# 1.net
KiCad netlist of a schematic drawn in Altium Designer
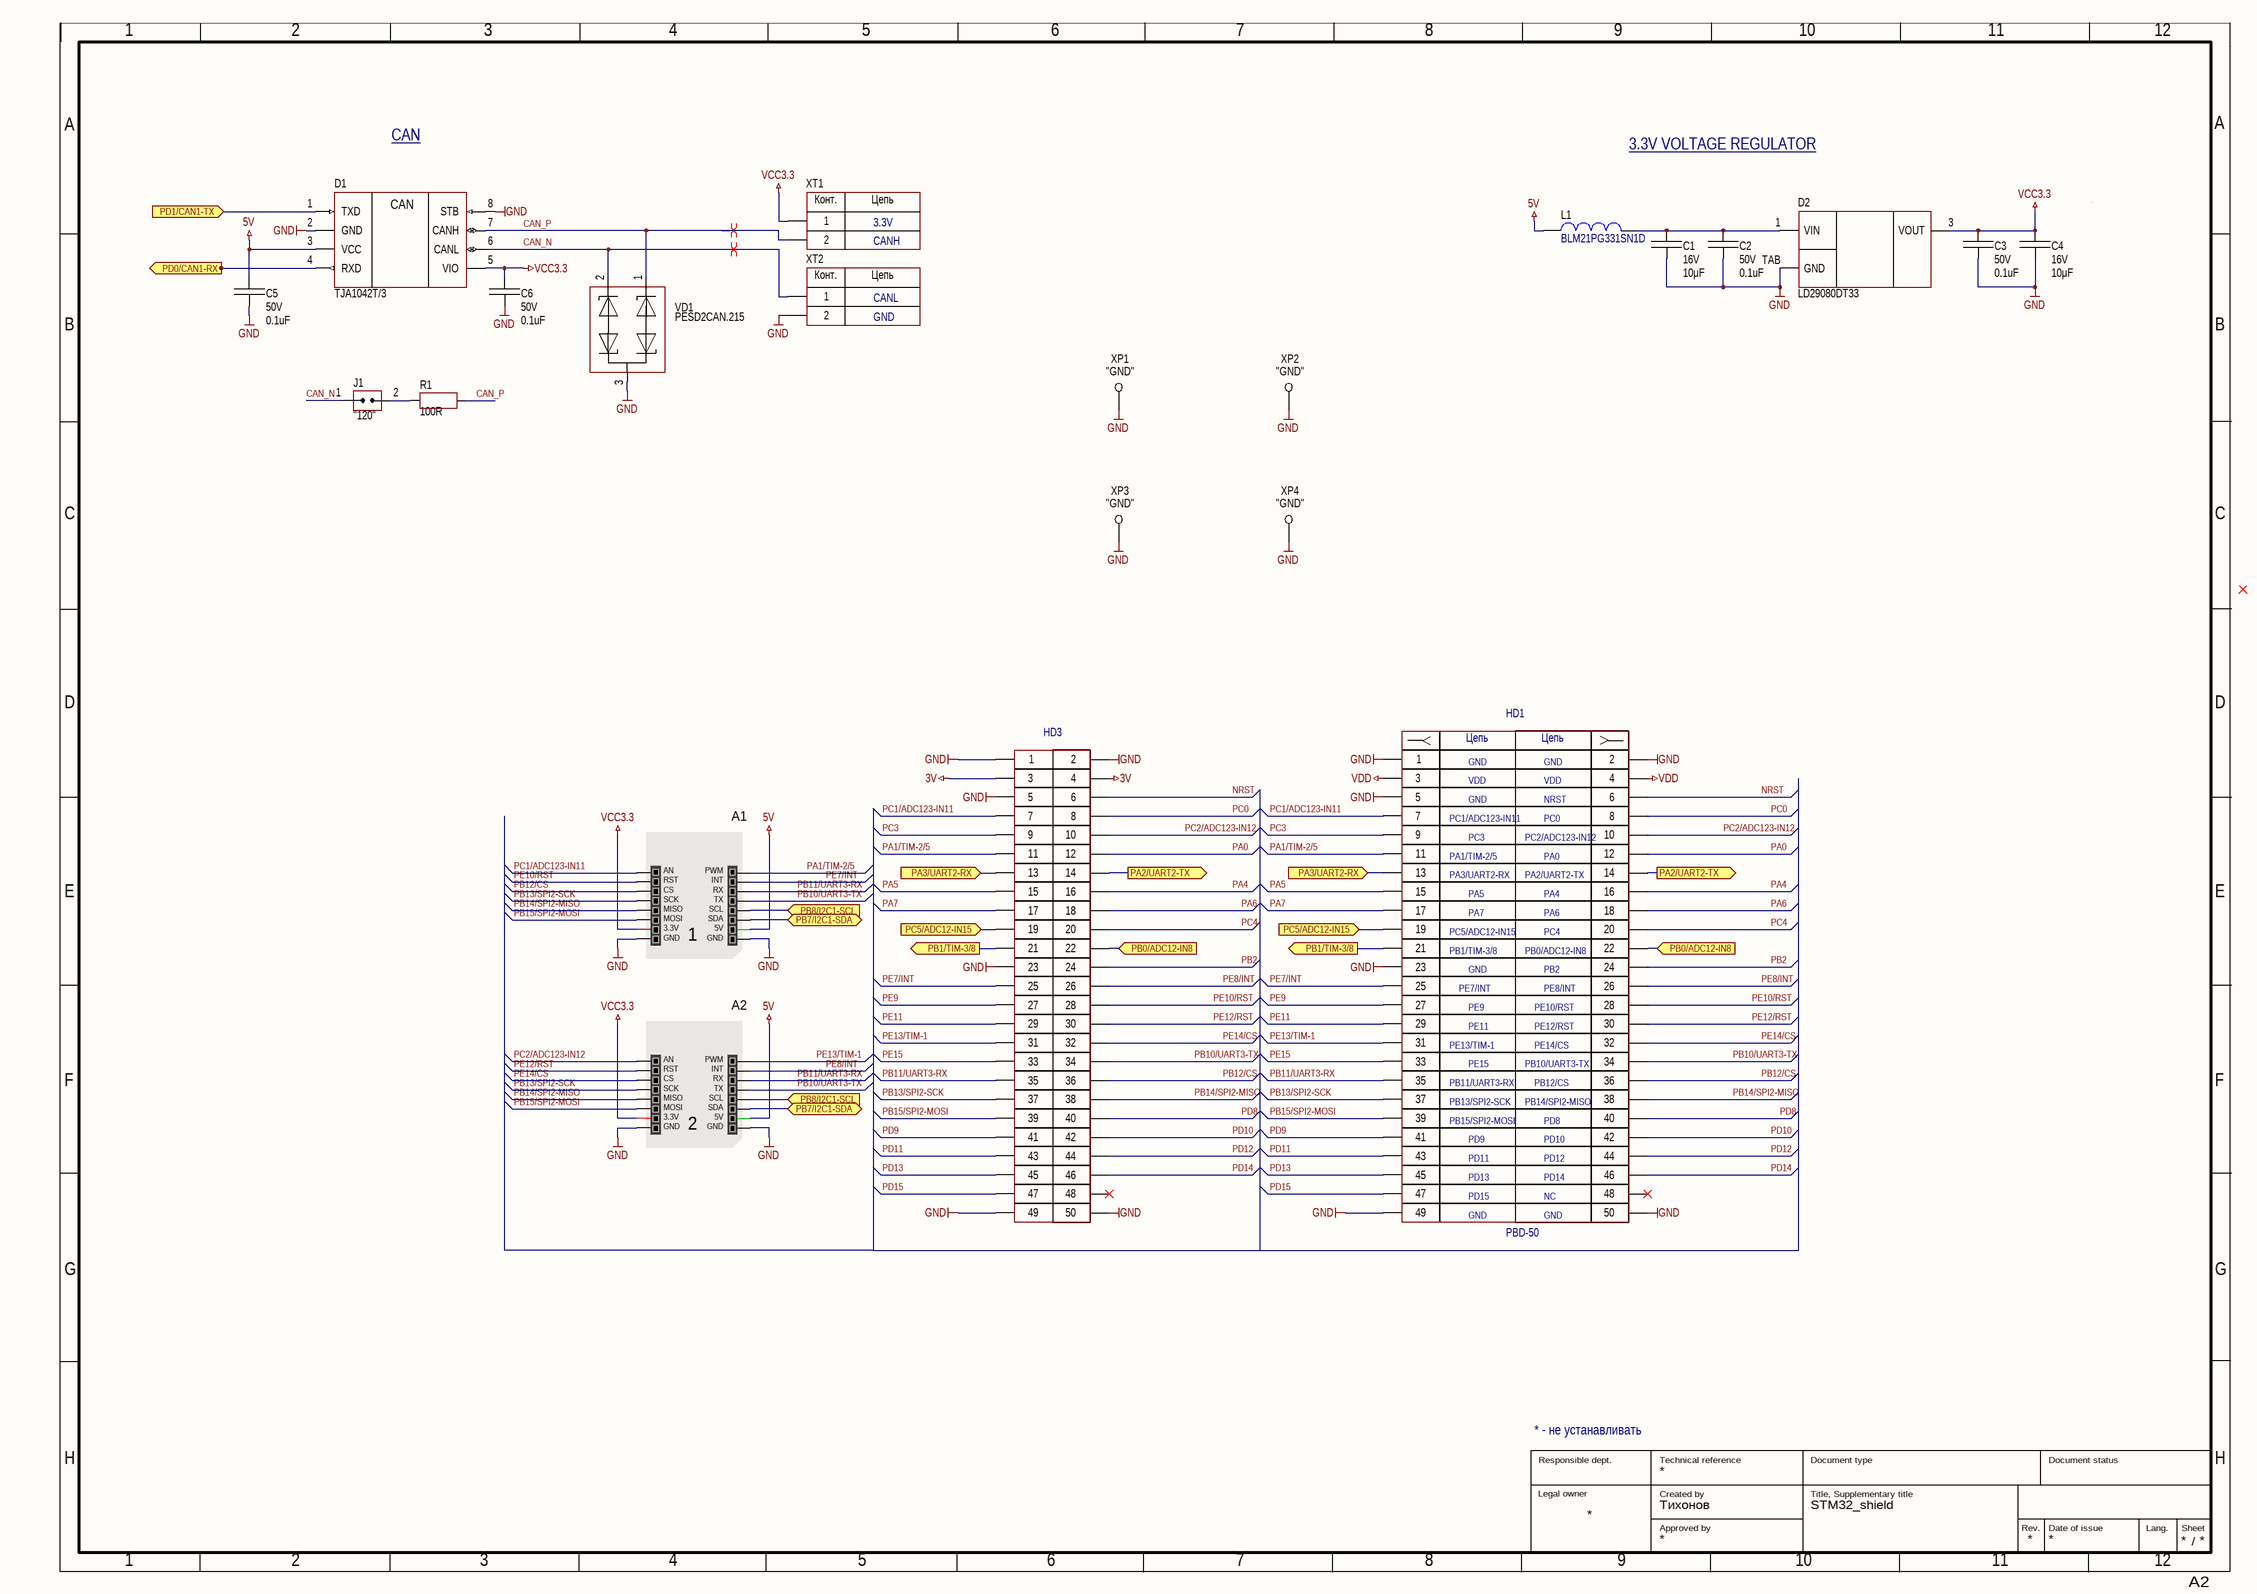
[diagram p0: Лист1.SchDoc]

(export (version "E")
  (design (tool "Eeschema 10.0.6"))
  (components
    (comp (ref "A1")
      (value "MIKROBUS HOST CONN._1")
      (footprint "MIKROBUS HOST CONN.")
      (description "mikroBUS Host Socket")
      (fields (field (name "PARTNUMBER") "PBS-8 (2pcs)") (field (name "MANUFACTURER") "Connfly"))
      (libsource (lib "Module") (part "MIKROBUS HOST CONN._1"))
    )
    (comp (ref "A2")
      (value "MIKROBUS HOST CONN._1")
      (footprint "MIKROBUS HOST CONN.")
      (description "mikroBUS Host Socket")
      (fields (field (name "PARTNUMBER") "PBS-8 (2pcs)") (field (name "MANUFACTURER") "Connfly"))
      (libsource (lib "Module") (part "MIKROBUS HOST CONN._1"))
    )
    (comp (ref "C1")
      (value "10μF")
      (footprint "StandardCase:CAP: TANTAL-A")
      (fields
        (field (name "MANUFACTURER") "AVX")
        (field (name "PARTNUMBER") "TAJB106K016RNJ")
        (field (name "VALUEMANUFACTURERPARTNUMBER") "Tantalum capacitor, 10μF, 16V, ±10%, 1.2Ohm, case B (3528), -55...+125°C")
        (field (name "VOLTAGE") "16V")
      )
      (libsource (lib "Capacitor") (part "Tantal_B"))
    )
    (comp (ref "C2")
      (value "0.1uF")
      (footprint "CAP: 0603")
      (fields
        (field (name "MANUFACTURER") "SAMSUNG")
        (field (name "PARTNUMBER") "CL10B104KB8NNNC")
        (field (name "VALUEMANUFACTURERPARTNUMBER") "Ceramic capacitor, 0.1uF, X7R, ±10%, 50V, 0603, -55...+125°C")
        (field (name "VOLTAGE") "50V")
      )
      (libsource (lib "Capacitor") (part "Ceramic_0603"))
    )
    (comp (ref "C3")
      (value "0.1uF")
      (footprint "CAP: 0603")
      (fields
        (field (name "MANUFACTURER") "SAMSUNG")
        (field (name "PARTNUMBER") "CL10B104KB8NNNC")
        (field (name "VALUEMANUFACTURERPARTNUMBER") "Ceramic capacitor, 0.1uF, X7R, ±10%, 50V, 0603, -55...+125°C")
        (field (name "VOLTAGE") "50V")
      )
      (libsource (lib "Capacitor") (part "Ceramic_0603"))
    )
    (comp (ref "C4")
      (value "10μF")
      (footprint "StandardCase:CAP: TANTAL-A")
      (fields
        (field (name "MANUFACTURER") "AVX")
        (field (name "PARTNUMBER") "TAJB106K016RNJ")
        (field (name "VALUEMANUFACTURERPARTNUMBER") "Tantalum capacitor, 10μF, 16V, ±10%, 1.2Ohm, case B (3528), -55...+125°C")
        (field (name "VOLTAGE") "16V")
      )
      (libsource (lib "Capacitor") (part "Tantal_B"))
    )
    (comp (ref "C5")
      (value "0.1uF")
      (footprint "CAP: 0603")
      (fields
        (field (name "MANUFACTURER") "SAMSUNG")
        (field (name "PARTNUMBER") "CL10B104KB8NNNC")
        (field (name "VALUEMANUFACTURERPARTNUMBER") "Ceramic capacitor, 0.1uF, X7R, ±10%, 50V, 0603, -55...+125°C")
        (field (name "VOLTAGE") "50V")
      )
      (libsource (lib "Capacitor") (part "Ceramic_0603"))
    )
    (comp (ref "C6")
      (value "0.1uF")
      (footprint "CAP: 0603")
      (fields
        (field (name "MANUFACTURER") "SAMSUNG")
        (field (name "PARTNUMBER") "CL10B104KB8NNNC")
        (field (name "VALUEMANUFACTURERPARTNUMBER") "Ceramic capacitor, 0.1uF, X7R, ±10%, 50V, 0603, -55...+125°C")
        (field (name "VOLTAGE") "50V")
      )
      (libsource (lib "Capacitor") (part "Ceramic_0603"))
    )
    (comp (ref "D1")
      (value "~")
      (footprint "StandardCase:8-SOIC")
      (description "CAN")
      (fields
        (field (name "MANUFACTURER") "NXP")
        (field (name "VALUEMANUFACTURERPARTNUMBER") "IC CAN transceiver, 5Mbps, , 5V, -40...+85°C, SO8")
        (field (name "PARTNUMBER") "TJA1042T/3")
      )
      (libsource (lib "IC. Interface") (part "TJA1042T/3"))
    )
    (comp (ref "D2")
      (value "~")
      (footprint "StandardCase:DPAK(LDO)")
      (description "Linear voltage regulator")
      (fields
        (field (name "MANUFACTURER") "STMicroelectronics")
        (field (name "VALUEMANUFACTURERPARTNUMBER") "Linear voltage regulator, input 4.3...8.8V, 0.4V, output 3.3V, 0.8A, -40...+85°C, DPAK(TO-252)")
        (field (name "PARTNUMBER") "LD29080DT33")
      )
      (libsource (lib "IC. Power supply") (part "LD29080DT33R"))
    )
    (comp (ref "HD1")
      (value "PBD-50")
      (footprint "CON: PBD-50")
      (description "Розетка в 2 ряда")
      (fields
        (field (name "MANUFACTURER") "Connfly Electronic")
        (field (name "PART_NUMBER") "PBD-50 (DS1023-2x25)")
        (field (name "PUBLISHER") "TEN")
      )
      (libsource (lib "Connector") (part "PBD-50"))
    )
    (comp (ref "HD3")
      (value "PBD-50-1")
      (footprint "CON: PBD-50_NOT3D")
      (description "Пустое место")
      (fields
        (field (name "MANUFACTURER") "Connfly Electronic")
        (field (name "PART_NUMBER") "PBD-50")
        (field (name "PUBLISHER") "TEN")
      )
      (libsource (lib "Connector") (part "PBD-50-1"))
    )
    (comp (ref "J1")
      (value "PLS-2")
      (footprint "CustomCase:CON: PLS-2")
      (fields (field (name "COMMENTTEXT") "\"120\""))
      (libsource (lib "Connector") (part "Jumper_single"))
    )
    (comp (ref "L1")
      (value "BLM21PG331SN1D")
      (footprint "StandardCase:IND: 0805")
      (fields
        (field (name "MANUFACTURER") "Murata Electronics")
        (field (name "VALUEMANUFACTURERPARTNUMBER") "Fixed inductor, 330Ohm@100Mhz, , 0805, 1500mA, -55...+125°C")
      )
      (libsource (lib "Inductor") (part "EMI_SMD"))
    )
    (comp (ref "R1")
      (value "100R")
      (footprint "RES: 0603")
      (fields
        (field (name "MANUFACTURER") "Yageo")
        (field (name "PARTNUMBER") "RC0603FR-07100RL")
        (field (name "VALUEMANUFACTURERPARTNUMBER") "Resistor film, 100R, ±1%, 0603, 0.1W, -55...+125°C")
      )
      (libsource (lib "Resistor") (part "Resistor_0603"))
    )
    (comp (ref "VD1")
      (value "~")
      (footprint "StandardCase:SOT23")
      (fields
        (field (name "MANUFACTURER") "NEXPERIA")
        (field (name "VALUEMANUFACTURERPARTNUMBER") "ESD Suppressors, , , , , SOT-23-3, -65...+150°C")
        (field (name "PARTNUMBER") "PESD2CAN.215")
      )
      (libsource (lib "Diode") (part "PESD2CAN"))
    )
    (comp (ref "XP1")
      (value "\"GND\"")
      (footprint "CON: PLS-1")
      (description "Вилка")
      (fields
        (field (name "PART_NUMBER") "PLS-1")
        (field (name "MANUFACTURER") "Ningbo connfly electronic (Zhenqin)")
        (field (name "PUBLISHER") "TEN")
      )
      (libsource (lib "Connector") (part "PLS-1"))
    )
    (comp (ref "XP2")
      (value "\"GND\"")
      (footprint "CON: PLS-1")
      (description "Вилка")
      (fields
        (field (name "PART_NUMBER") "PLS-1")
        (field (name "MANUFACTURER") "Ningbo connfly electronic (Zhenqin)")
        (field (name "PUBLISHER") "TEN")
      )
      (libsource (lib "Connector") (part "PLS-1"))
    )
    (comp (ref "XP3")
      (value "\"GND\"")
      (footprint "CON: PLS-1")
      (description "Вилка")
      (fields
        (field (name "PART_NUMBER") "PLS-1")
        (field (name "MANUFACTURER") "Ningbo connfly electronic (Zhenqin)")
        (field (name "PUBLISHER") "TEN")
      )
      (libsource (lib "Connector") (part "PLS-1"))
    )
    (comp (ref "XP4")
      (value "\"GND\"")
      (footprint "CON: PLS-1")
      (description "Вилка")
      (fields
        (field (name "PART_NUMBER") "PLS-1")
        (field (name "MANUFACTURER") "Ningbo connfly electronic (Zhenqin)")
        (field (name "PUBLISHER") "TEN")
      )
      (libsource (lib "Connector") (part "PLS-1"))
    )
    (comp (ref "XT1")
      (value "~")
      (footprint "CON: MPT 0,5/ 2-2,54 (Phoenix)")
      (fields
        (field (name "MANUFACTURER") "Китай")
        (field (name "VALUEMANUFACTURERPARTNUMBER") "Клеммник винтовой, 2pin, 2.54m, 250В, 8A")
        (field (name "PARTNUMBER") "308-021-14")
      )
      (libsource (lib "Connector") (part "Connector_terminal_2pin"))
    )
    (comp (ref "XT2")
      (value "~")
      (footprint "CON: MPT 0,5/ 2-2,54 (Phoenix)")
      (fields
        (field (name "MANUFACTURER") "Китай")
        (field (name "VALUEMANUFACTURERPARTNUMBER") "Клеммник винтовой, 2pin, 2.54m, 250В, 8A")
        (field (name "PARTNUMBER") "308-021-14")
      )
      (libsource (lib "Connector") (part "Connector_terminal_2pin"))
    )
  )
  (nets
    (net (code "1") (name "/CAN_N") (class "Default")
      (node (ref "D1") (pin "6") (pinfunction "CANL_6") (pintype "bidirectional"))
      (node (ref "J1") (pin "1") (pinfunction "IN_1") (pintype "passive"))
      (node (ref "VD1") (pin "2") (pintype "passive"))
      (node (ref "XT2") (pin "1") (pinfunction "1_1") (pintype "passive"))
    )
    (net (code "2") (name "/CAN_P") (class "Default")
      (node (ref "D1") (pin "7") (pinfunction "CANH_7") (pintype "bidirectional"))
      (node (ref "R1") (pin "2") (pinfunction "2_2") (pintype "passive"))
      (node (ref "VD1") (pin "1") (pintype "passive"))
      (node (ref "XT1") (pin "2") (pinfunction "2_2") (pintype "passive"))
    )
    (net (code "3") (name "/NRST") (class "Default")
      (node (ref "HD1") (pin "6") (pinfunction "6_6") (pintype "passive"))
      (node (ref "HD3") (pin "6") (pinfunction "6_6") (pintype "passive"))
    )
    (net (code "4") (name "/PA0") (class "Default")
      (node (ref "HD1") (pin "12") (pinfunction "12_12") (pintype "passive"))
      (node (ref "HD3") (pin "12") (pinfunction "12_12") (pintype "passive"))
    )
    (net (code "5") (name "/PA1{slash}TIM-2{slash}5") (class "Default")
      (node (ref "A1") (pin "16") (pinfunction "PWM_16") (pintype "passive"))
      (node (ref "HD1") (pin "11") (pinfunction "11_11") (pintype "passive"))
      (node (ref "HD3") (pin "11") (pinfunction "11_11") (pintype "passive"))
    )
    (net (code "6") (name "/PA2{slash}UART2-TX") (class "Default")
      (node (ref "HD1") (pin "14") (pinfunction "14_14") (pintype "passive"))
      (node (ref "HD3") (pin "14") (pinfunction "14_14") (pintype "passive"))
    )
    (net (code "7") (name "/PA3{slash}UART2-RX") (class "Default")
      (node (ref "HD1") (pin "13") (pinfunction "13_13") (pintype "passive"))
      (node (ref "HD3") (pin "13") (pinfunction "13_13") (pintype "passive"))
    )
    (net (code "8") (name "/PA4") (class "Default")
      (node (ref "HD1") (pin "16") (pinfunction "16_16") (pintype "passive"))
      (node (ref "HD3") (pin "16") (pinfunction "16_16") (pintype "passive"))
    )
    (net (code "9") (name "/PA5") (class "Default")
      (node (ref "HD1") (pin "15") (pinfunction "15_15") (pintype "passive"))
      (node (ref "HD3") (pin "15") (pinfunction "15_15") (pintype "passive"))
    )
    (net (code "10") (name "/PA6") (class "Default")
      (node (ref "HD1") (pin "18") (pinfunction "18_18") (pintype "passive"))
      (node (ref "HD3") (pin "18") (pinfunction "18_18") (pintype "passive"))
    )
    (net (code "11") (name "/PA7") (class "Default")
      (node (ref "HD1") (pin "17") (pinfunction "17_17") (pintype "passive"))
      (node (ref "HD3") (pin "17") (pinfunction "17_17") (pintype "passive"))
    )
    (net (code "12") (name "/PB0{slash}ADC12-IN8") (class "Default")
      (node (ref "HD1") (pin "22") (pinfunction "22_22") (pintype "passive"))
      (node (ref "HD3") (pin "22") (pinfunction "22_22") (pintype "passive"))
    )
    (net (code "13") (name "/PB1{slash}TIM-3{slash}8") (class "Default")
      (node (ref "HD1") (pin "21") (pinfunction "21_21") (pintype "passive"))
      (node (ref "HD3") (pin "21") (pinfunction "21_21") (pintype "passive"))
    )
    (net (code "14") (name "/PB2") (class "Default")
      (node (ref "HD1") (pin "24") (pinfunction "24_24") (pintype "passive"))
      (node (ref "HD3") (pin "24") (pinfunction "24_24") (pintype "passive"))
    )
    (net (code "15") (name "/PB7{slash}I2C1-SDA") (class "Default")
      (node (ref "A1") (pin "11") (pinfunction "SDA_11") (pintype "passive"))
      (node (ref "A2") (pin "11") (pinfunction "SDA_11") (pintype "passive"))
    )
    (net (code "16") (name "/PB8{slash}I2C1-SCL") (class "Default")
      (node (ref "A1") (pin "12") (pinfunction "SCL_12") (pintype "passive"))
      (node (ref "A2") (pin "12") (pinfunction "SCL_12") (pintype "passive"))
    )
    (net (code "17") (name "/PB10{slash}UART3-TX") (class "Default")
      (node (ref "A1") (pin "13") (pinfunction "TX_13") (pintype "passive"))
      (node (ref "A2") (pin "13") (pinfunction "TX_13") (pintype "passive"))
      (node (ref "HD1") (pin "34") (pinfunction "34_34") (pintype "passive"))
      (node (ref "HD3") (pin "34") (pinfunction "34_34") (pintype "passive"))
    )
    (net (code "18") (name "/PB11{slash}UART3-RX") (class "Default")
      (node (ref "A1") (pin "14") (pinfunction "RX_14") (pintype "passive"))
      (node (ref "A2") (pin "14") (pinfunction "RX_14") (pintype "passive"))
      (node (ref "HD1") (pin "35") (pinfunction "35_35") (pintype "passive"))
      (node (ref "HD3") (pin "35") (pinfunction "35_35") (pintype "passive"))
    )
    (net (code "19") (name "/PB12{slash}CS") (class "Default")
      (node (ref "A1") (pin "3") (pinfunction "CS_3") (pintype "passive"))
      (node (ref "HD1") (pin "36") (pinfunction "36_36") (pintype "passive"))
      (node (ref "HD3") (pin "36") (pinfunction "36_36") (pintype "passive"))
    )
    (net (code "20") (name "/PB13{slash}SPI2-SCK") (class "Default")
      (node (ref "A1") (pin "4") (pinfunction "SCK_4") (pintype "passive"))
      (node (ref "A2") (pin "4") (pinfunction "SCK_4") (pintype "passive"))
      (node (ref "HD1") (pin "37") (pinfunction "37_37") (pintype "passive"))
      (node (ref "HD3") (pin "37") (pinfunction "37_37") (pintype "passive"))
    )
    (net (code "21") (name "/PB14{slash}SPI2-MISO") (class "Default")
      (node (ref "A1") (pin "5") (pinfunction "MISO_5") (pintype "passive"))
      (node (ref "A2") (pin "5") (pinfunction "MISO_5") (pintype "passive"))
      (node (ref "HD1") (pin "38") (pinfunction "38_38") (pintype "passive"))
      (node (ref "HD3") (pin "38") (pinfunction "38_38") (pintype "passive"))
    )
    (net (code "22") (name "/PB15{slash}SPI2-MOSI") (class "Default")
      (node (ref "A1") (pin "6") (pinfunction "MOSI_6") (pintype "passive"))
      (node (ref "A2") (pin "6") (pinfunction "MOSI_6") (pintype "passive"))
      (node (ref "HD1") (pin "39") (pinfunction "39_39") (pintype "passive"))
      (node (ref "HD3") (pin "39") (pinfunction "39_39") (pintype "passive"))
    )
    (net (code "23") (name "/PC0") (class "Default")
      (node (ref "HD1") (pin "8") (pinfunction "8_8") (pintype "passive"))
      (node (ref "HD3") (pin "8") (pinfunction "8_8") (pintype "passive"))
    )
    (net (code "24") (name "/PC1{slash}ADC123-IN11") (class "Default")
      (node (ref "A1") (pin "1") (pinfunction "AN_1") (pintype "passive"))
      (node (ref "HD1") (pin "7") (pinfunction "7_7") (pintype "passive"))
      (node (ref "HD3") (pin "7") (pinfunction "7_7") (pintype "passive"))
    )
    (net (code "25") (name "/PC2{slash}ADC123-IN12") (class "Default")
      (node (ref "A2") (pin "1") (pinfunction "AN_1") (pintype "passive"))
      (node (ref "HD1") (pin "10") (pinfunction "10_10") (pintype "passive"))
      (node (ref "HD3") (pin "10") (pinfunction "10_10") (pintype "passive"))
    )
    (net (code "26") (name "/PC3") (class "Default")
      (node (ref "HD1") (pin "9") (pinfunction "9_9") (pintype "passive"))
      (node (ref "HD3") (pin "9") (pinfunction "9_9") (pintype "passive"))
    )
    (net (code "27") (name "/PC4") (class "Default")
      (node (ref "HD1") (pin "20") (pinfunction "20_20") (pintype "passive"))
      (node (ref "HD3") (pin "20") (pinfunction "20_20") (pintype "passive"))
    )
    (net (code "28") (name "/PC5{slash}ADC12-IN15") (class "Default")
      (node (ref "HD1") (pin "19") (pinfunction "19_19") (pintype "passive"))
      (node (ref "HD3") (pin "19") (pinfunction "19_19") (pintype "passive"))
    )
    (net (code "29") (name "/PD0{slash}CAN1-RX") (class "Default")
      (node (ref "D1") (pin "4") (pinfunction "RXD_4") (pintype "output"))
    )
    (net (code "30") (name "/PD1{slash}CAN1-TX") (class "Default")
      (node (ref "D1") (pin "1") (pinfunction "TXD_1") (pintype "input"))
    )
    (net (code "31") (name "/PD8") (class "Default")
      (node (ref "HD1") (pin "40") (pinfunction "40_40") (pintype "passive"))
      (node (ref "HD3") (pin "40") (pinfunction "40_40") (pintype "passive"))
    )
    (net (code "32") (name "/PD9") (class "Default")
      (node (ref "HD1") (pin "41") (pinfunction "41_41") (pintype "passive"))
      (node (ref "HD3") (pin "41") (pinfunction "41_41") (pintype "passive"))
    )
    (net (code "33") (name "/PD10") (class "Default")
      (node (ref "HD1") (pin "42") (pinfunction "42_42") (pintype "passive"))
      (node (ref "HD3") (pin "42") (pinfunction "42_42") (pintype "passive"))
    )
    (net (code "34") (name "/PD11") (class "Default")
      (node (ref "HD1") (pin "43") (pinfunction "43_43") (pintype "passive"))
      (node (ref "HD3") (pin "43") (pinfunction "43_43") (pintype "passive"))
    )
    (net (code "35") (name "/PD12") (class "Default")
      (node (ref "HD1") (pin "44") (pinfunction "44_44") (pintype "passive"))
      (node (ref "HD3") (pin "44") (pinfunction "44_44") (pintype "passive"))
    )
    (net (code "36") (name "/PD13") (class "Default")
      (node (ref "HD1") (pin "45") (pinfunction "45_45") (pintype "passive"))
      (node (ref "HD3") (pin "45") (pinfunction "45_45") (pintype "passive"))
    )
    (net (code "37") (name "/PD14") (class "Default")
      (node (ref "HD1") (pin "46") (pinfunction "46_46") (pintype "passive"))
      (node (ref "HD3") (pin "46") (pinfunction "46_46") (pintype "passive"))
    )
    (net (code "38") (name "/PD15") (class "Default")
      (node (ref "HD1") (pin "47") (pinfunction "47_47") (pintype "passive"))
      (node (ref "HD3") (pin "47") (pinfunction "47_47") (pintype "passive"))
    )
    (net (code "39") (name "/PE7{slash}INT") (class "Default")
      (node (ref "A1") (pin "15") (pinfunction "INT_15") (pintype "passive"))
      (node (ref "HD1") (pin "25") (pinfunction "25_25") (pintype "passive"))
      (node (ref "HD3") (pin "25") (pinfunction "25_25") (pintype "passive"))
    )
    (net (code "40") (name "/PE8{slash}INT") (class "Default")
      (node (ref "A2") (pin "15") (pinfunction "INT_15") (pintype "passive"))
      (node (ref "HD1") (pin "26") (pinfunction "26_26") (pintype "passive"))
      (node (ref "HD3") (pin "26") (pinfunction "26_26") (pintype "passive"))
    )
    (net (code "41") (name "/PE9") (class "Default")
      (node (ref "HD1") (pin "27") (pinfunction "27_27") (pintype "passive"))
      (node (ref "HD3") (pin "27") (pinfunction "27_27") (pintype "passive"))
    )
    (net (code "42") (name "/PE10{slash}RST") (class "Default")
      (node (ref "A1") (pin "2") (pinfunction "RST_2") (pintype "passive"))
      (node (ref "HD1") (pin "28") (pinfunction "28_28") (pintype "passive"))
      (node (ref "HD3") (pin "28") (pinfunction "28_28") (pintype "passive"))
    )
    (net (code "43") (name "/PE11") (class "Default")
      (node (ref "HD1") (pin "29") (pinfunction "29_29") (pintype "passive"))
      (node (ref "HD3") (pin "29") (pinfunction "29_29") (pintype "passive"))
    )
    (net (code "44") (name "/PE12{slash}RST") (class "Default")
      (node (ref "A2") (pin "2") (pinfunction "RST_2") (pintype "passive"))
      (node (ref "HD1") (pin "30") (pinfunction "30_30") (pintype "passive"))
      (node (ref "HD3") (pin "30") (pinfunction "30_30") (pintype "passive"))
    )
    (net (code "45") (name "/PE13{slash}TIM-1") (class "Default")
      (node (ref "A2") (pin "16") (pinfunction "PWM_16") (pintype "passive"))
      (node (ref "HD1") (pin "31") (pinfunction "31_31") (pintype "passive"))
      (node (ref "HD3") (pin "31") (pinfunction "31_31") (pintype "passive"))
    )
    (net (code "46") (name "/PE14{slash}CS") (class "Default")
      (node (ref "A2") (pin "3") (pinfunction "CS_3") (pintype "passive"))
      (node (ref "HD1") (pin "32") (pinfunction "32_32") (pintype "passive"))
      (node (ref "HD3") (pin "32") (pinfunction "32_32") (pintype "passive"))
    )
    (net (code "47") (name "/PE15") (class "Default")
      (node (ref "HD1") (pin "33") (pinfunction "33_33") (pintype "passive"))
      (node (ref "HD3") (pin "33") (pinfunction "33_33") (pintype "passive"))
    )
    (net (code "48") (name "3V") (class "Default")
      (node (ref "HD3") (pin "3") (pinfunction "3_3") (pintype "passive"))
      (node (ref "HD3") (pin "4") (pinfunction "4_4") (pintype "passive"))
    )
    (net (code "49") (name "5V") (class "Default")
      (node (ref "A1") (pin "10") (pinfunction "5V_10") (pintype "passive"))
      (node (ref "A2") (pin "10") (pinfunction "5V_10") (pintype "passive"))
      (node (ref "C5") (pin "2") (pinfunction "2_2") (pintype "power_in"))
      (node (ref "D1") (pin "3") (pinfunction "VCC_3") (pintype "passive"))
      (node (ref "L1") (pin "2") (pinfunction "2_2") (pintype "passive"))
    )
    (net (code "50") (name "GND") (class "Default")
      (node (ref "A1") (pin "8") (pinfunction "GND_8") (pintype "passive"))
      (node (ref "A1") (pin "9") (pinfunction "GND_9") (pintype "passive"))
      (node (ref "A2") (pin "8") (pinfunction "GND_8") (pintype "passive"))
      (node (ref "A2") (pin "9") (pinfunction "GND_9") (pintype "passive"))
      (node (ref "C1") (pin "1") (pinfunction "1_1") (pintype "power_in"))
      (node (ref "C2") (pin "1") (pinfunction "1_1") (pintype "power_in"))
      (node (ref "C3") (pin "1") (pinfunction "1_1") (pintype "power_in"))
      (node (ref "C4") (pin "1") (pinfunction "1_1") (pintype "power_in"))
      (node (ref "C5") (pin "1") (pinfunction "1_1") (pintype "power_in"))
      (node (ref "C6") (pin "1") (pinfunction "1_1") (pintype "power_in"))
      (node (ref "D1") (pin "2") (pinfunction "GND_2") (pintype "passive"))
      (node (ref "D1") (pin "8") (pinfunction "STB_8") (pintype "input"))
      (node (ref "D2") (pin "TAB") (pinfunction "GND_TAB") (pintype "power_in"))
      (node (ref "HD1") (pin "1") (pinfunction "1_1") (pintype "passive"))
      (node (ref "HD1") (pin "2") (pinfunction "2_2") (pintype "passive"))
      (node (ref "HD1") (pin "23") (pinfunction "23_23") (pintype "passive"))
      (node (ref "HD1") (pin "49") (pinfunction "49_49") (pintype "passive"))
      (node (ref "HD1") (pin "5") (pinfunction "5_5") (pintype "passive"))
      (node (ref "HD1") (pin "50") (pinfunction "50_50") (pintype "passive"))
      (node (ref "HD3") (pin "1") (pinfunction "1_1") (pintype "passive"))
      (node (ref "HD3") (pin "2") (pinfunction "2_2") (pintype "passive"))
      (node (ref "HD3") (pin "23") (pinfunction "23_23") (pintype "passive"))
      (node (ref "HD3") (pin "49") (pinfunction "49_49") (pintype "passive"))
      (node (ref "HD3") (pin "5") (pinfunction "5_5") (pintype "passive"))
      (node (ref "HD3") (pin "50") (pinfunction "50_50") (pintype "passive"))
      (node (ref "VD1") (pin "3") (pintype "passive"))
      (node (ref "XP1") (pin "1") (pinfunction "1_1") (pintype "passive"))
      (node (ref "XP2") (pin "1") (pinfunction "1_1") (pintype "passive"))
      (node (ref "XP3") (pin "1") (pinfunction "1_1") (pintype "passive"))
      (node (ref "XP4") (pin "1") (pinfunction "1_1") (pintype "passive"))
      (node (ref "XT2") (pin "2") (pinfunction "2_2") (pintype "passive"))
    )
    (net (code "51") (name "Net-(D2-VIN)") (class "Default")
      (node (ref "C1") (pin "2") (pinfunction "2_2") (pintype "power_in"))
      (node (ref "C2") (pin "2") (pinfunction "2_2") (pintype "power_in"))
      (node (ref "D2") (pin "1") (pinfunction "VIN_1") (pintype "power_in"))
      (node (ref "L1") (pin "1") (pinfunction "1_1") (pintype "passive"))
    )
    (net (code "52") (name "Net-(J1-IN-Pad2)") (class "Default")
      (node (ref "J1") (pin "2") (pinfunction "IN_2") (pintype "passive"))
      (node (ref "R1") (pin "1") (pinfunction "1_1") (pintype "passive"))
    )
    (net (code "53") (name "VCC3.3") (class "Default")
      (node (ref "A1") (pin "7") (pinfunction "3.3V_7") (pintype "passive"))
      (node (ref "A2") (pin "7") (pinfunction "3.3V_7") (pintype "passive"))
      (node (ref "C3") (pin "2") (pinfunction "2_2") (pintype "power_in"))
      (node (ref "C4") (pin "2") (pinfunction "2_2") (pintype "power_in"))
      (node (ref "C6") (pin "2") (pinfunction "2_2") (pintype "power_in"))
      (node (ref "D1") (pin "5") (pinfunction "VIO_5") (pintype "power_in"))
      (node (ref "D2") (pin "3") (pinfunction "VOUT_3") (pintype "power_in"))
      (node (ref "XT1") (pin "1") (pinfunction "1_1") (pintype "passive"))
    )
    (net (code "54") (name "VDD") (class "Default")
      (node (ref "HD1") (pin "3") (pinfunction "3_3") (pintype "passive"))
      (node (ref "HD1") (pin "4") (pinfunction "4_4") (pintype "passive"))
    )
    (net (code "55") (name "unconnected-(HD1-Pad48)") (class "Default")
      (node (ref "HD1") (pin "48") (pinfunction "48_48") (pintype "passive+no_connect"))
    )
    (net (code "56") (name "unconnected-(HD3-Pad48)") (class "Default")
      (node (ref "HD3") (pin "48") (pinfunction "48_48") (pintype "passive+no_connect"))
    )
  )
)
